# 04-SX1257.net
KiCad netlist of a schematic drawn in Altium Designer
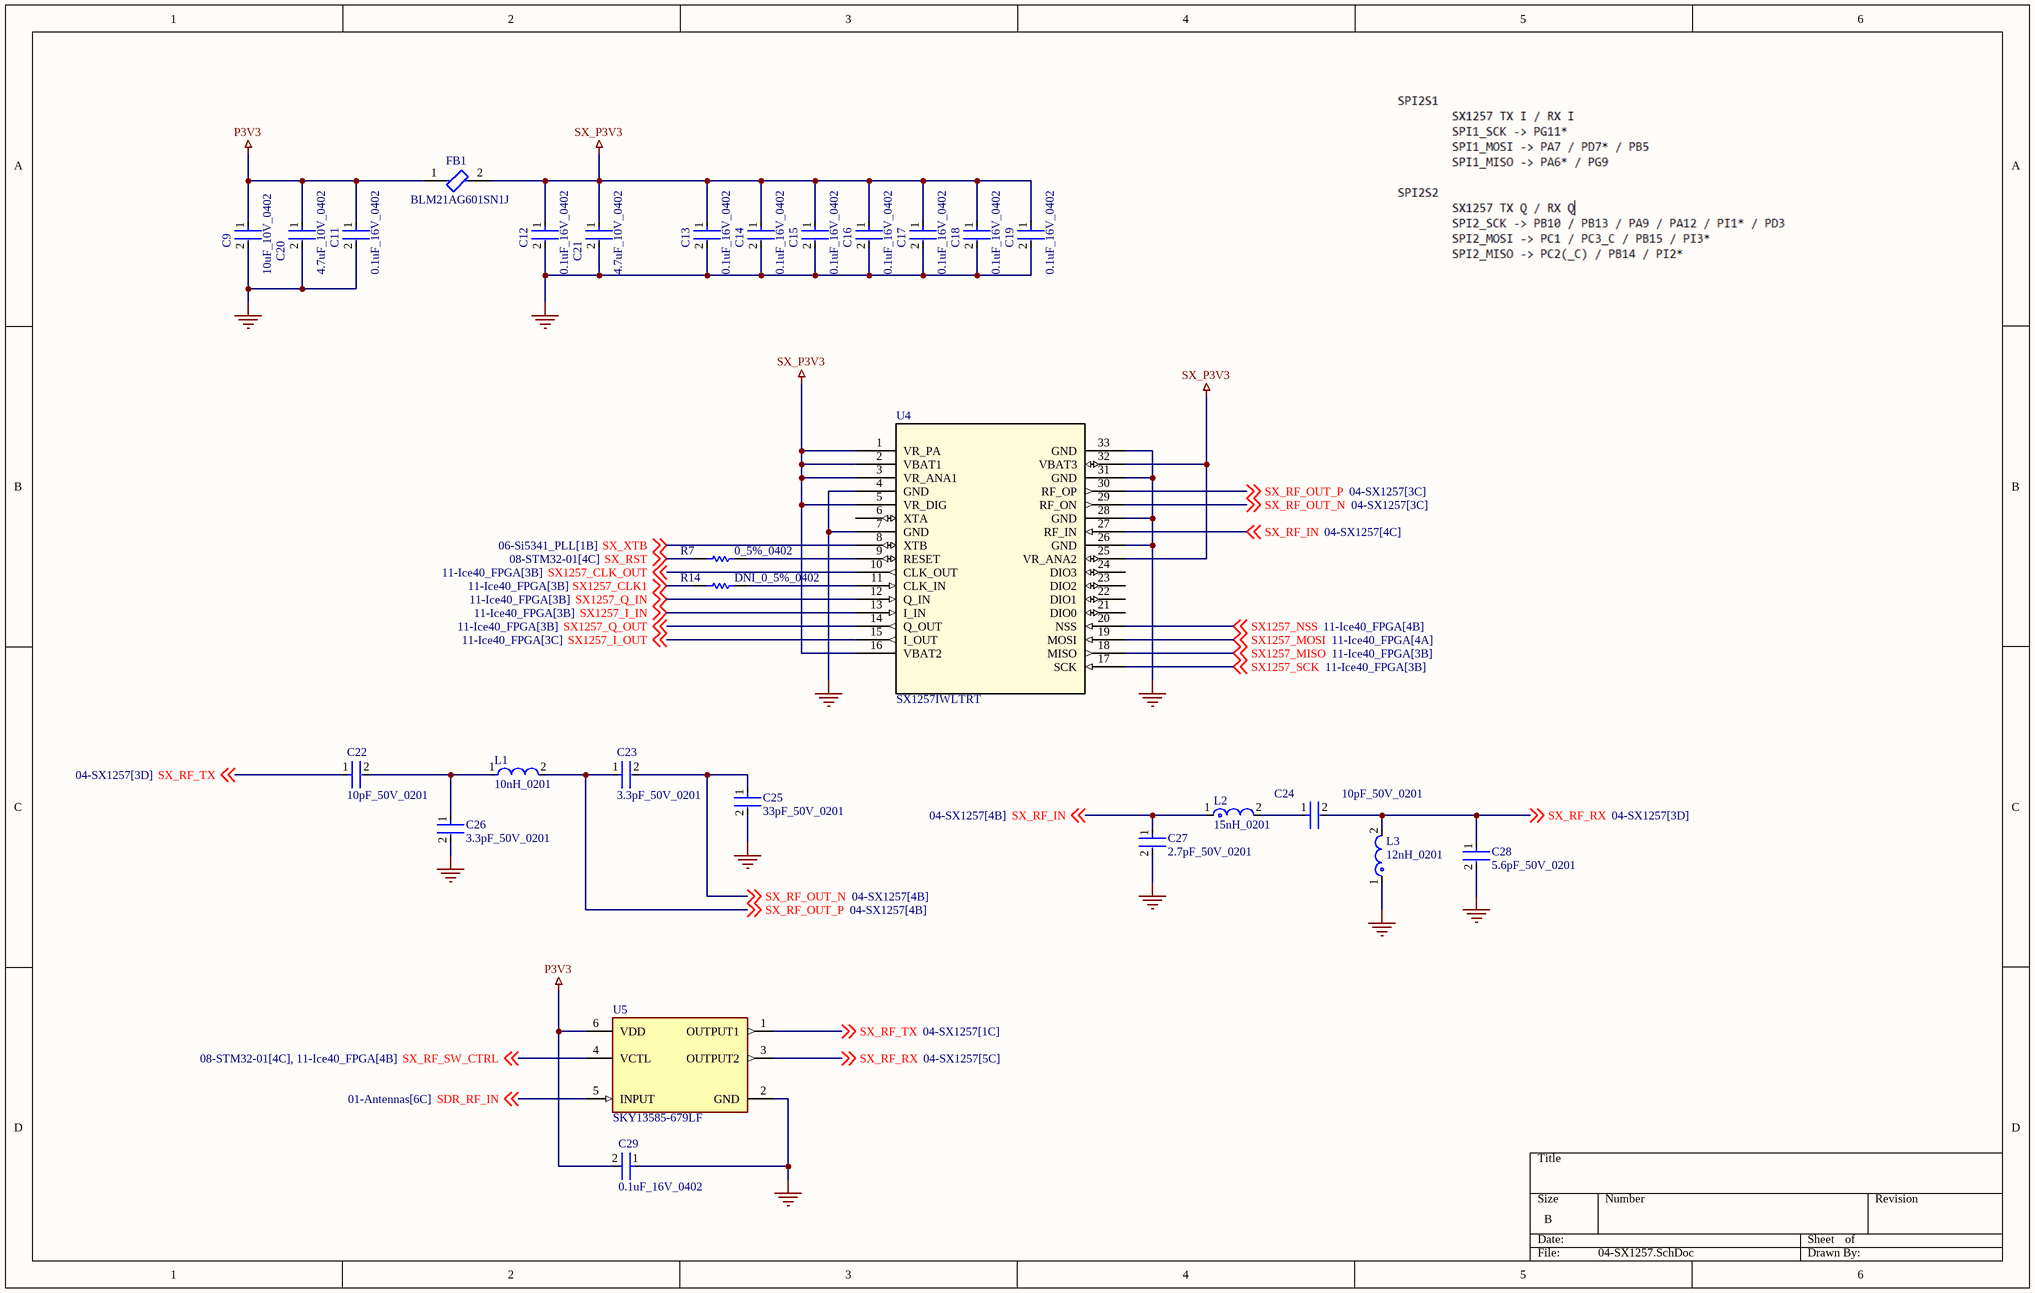
[diagram p0: 04-SX1257.SchDoc]

(export (version "E")
  (design (tool "Eeschema 10.0.6"))
  (components
    (comp (ref "C9")
      (value "10uF_10V_0402")
      (footprint "FP-CL05A106MP5NUNC-MFG")
      (description "CAP CER 10UF 10V X5R 0402")
      (fields
        (field (name "OCTOPART") "https://octopart.com/cl05a106mp5nunc-samsung-22457395")
        (field (name "TOLERANCE") "20%")
      )
      (libsource (lib "Altium Content Vault") (part "b4654b650e69147ec39a6b967a45e02"))
    )
    (comp (ref "C11")
      (value "0.1uF_16V_0402")
      (footprint "FP-C0402-BB-MFG")
      (description "CAP CER 0.1UF 16V 5% X7R 0402")
      (fields
        (field (name "MANUFACTURER") "Kemet")
        (field (name "MANUFACTURER PART NUMBER") "C0402C104J4RACTU")
      )
      (libsource (lib "Altium Content Vault") (part "b4654b650e69147ec39a6b967a45e02"))
    )
    (comp (ref "C12")
      (value "0.1uF_16V_0402")
      (footprint "FP-C0402-BB-MFG")
      (description "CAP CER 0.1UF 16V 5% X7R 0402")
      (fields
        (field (name "MANUFACTURER") "Kemet")
        (field (name "MANUFACTURER PART NUMBER") "C0402C104J4RACTU")
      )
      (libsource (lib "Altium Content Vault") (part "b4654b650e69147ec39a6b967a45e02"))
    )
    (comp (ref "C13")
      (value "0.1uF_16V_0402")
      (footprint "FP-C0402-BB-MFG")
      (description "CAP CER 0.1UF 16V 5% X7R 0402")
      (fields
        (field (name "MANUFACTURER") "Kemet")
        (field (name "MANUFACTURER PART NUMBER") "C0402C104J4RACTU")
      )
      (libsource (lib "Altium Content Vault") (part "b4654b650e69147ec39a6b967a45e02"))
    )
    (comp (ref "C14")
      (value "0.1uF_16V_0402")
      (footprint "FP-C0402-BB-MFG")
      (description "CAP CER 0.1UF 16V 5% X7R 0402")
      (fields
        (field (name "MANUFACTURER") "Kemet")
        (field (name "MANUFACTURER PART NUMBER") "C0402C104J4RACTU")
      )
      (libsource (lib "Altium Content Vault") (part "b4654b650e69147ec39a6b967a45e02"))
    )
    (comp (ref "C15")
      (value "0.1uF_16V_0402")
      (footprint "FP-C0402-BB-MFG")
      (description "CAP CER 0.1UF 16V 5% X7R 0402")
      (fields
        (field (name "MANUFACTURER") "Kemet")
        (field (name "MANUFACTURER PART NUMBER") "C0402C104J4RACTU")
      )
      (libsource (lib "Altium Content Vault") (part "b4654b650e69147ec39a6b967a45e02"))
    )
    (comp (ref "C16")
      (value "0.1uF_16V_0402")
      (footprint "FP-C0402-BB-MFG")
      (description "CAP CER 0.1UF 16V 5% X7R 0402")
      (fields
        (field (name "MANUFACTURER") "Kemet")
        (field (name "MANUFACTURER PART NUMBER") "C0402C104J4RACTU")
      )
      (libsource (lib "Altium Content Vault") (part "b4654b650e69147ec39a6b967a45e02"))
    )
    (comp (ref "C17")
      (value "0.1uF_16V_0402")
      (footprint "FP-C0402-BB-MFG")
      (description "CAP CER 0.1UF 16V 5% X7R 0402")
      (fields
        (field (name "MANUFACTURER") "Kemet")
        (field (name "MANUFACTURER PART NUMBER") "C0402C104J4RACTU")
      )
      (libsource (lib "Altium Content Vault") (part "b4654b650e69147ec39a6b967a45e02"))
    )
    (comp (ref "C18")
      (value "0.1uF_16V_0402")
      (footprint "FP-C0402-BB-MFG")
      (description "CAP CER 0.1UF 16V 5% X7R 0402")
      (fields
        (field (name "MANUFACTURER") "Kemet")
        (field (name "MANUFACTURER PART NUMBER") "C0402C104J4RACTU")
      )
      (libsource (lib "Altium Content Vault") (part "b4654b650e69147ec39a6b967a45e02"))
    )
    (comp (ref "C19")
      (value "0.1uF_16V_0402")
      (footprint "FP-C0402-BB-MFG")
      (description "CAP CER 0.1UF 16V 5% X7R 0402")
      (fields
        (field (name "MANUFACTURER") "Kemet")
        (field (name "MANUFACTURER PART NUMBER") "C0402C104J4RACTU")
      )
      (libsource (lib "Altium Content Vault") (part "b4654b650e69147ec39a6b967a45e02"))
    )
    (comp (ref "C20")
      (value "4.7uF_10V_0402")
      (footprint "FP-C1005-050-0_15-MFG")
      (description "CAP CER 4.7UF 10V X5R 0402")
      (fields (field (name "TOLERANCE") "10%"))
      (libsource (lib "Altium Content Vault") (part "b4654b650e69147ec39a6b967a45e02"))
    )
    (comp (ref "C21")
      (value "4.7uF_10V_0402")
      (footprint "FP-C1005-050-0_15-MFG")
      (description "CAP CER 4.7UF 10V X5R 0402")
      (fields (field (name "TOLERANCE") "10%"))
      (libsource (lib "Altium Content Vault") (part "b4654b650e69147ec39a6b967a45e02"))
    )
    (comp (ref "C22")
      (value "10pF_50V_0201")
      (footprint "FP-CGA1A-0_1-0_03-MFG")
      (description "Cap Ceramic 10pF 50V C0G 0.5pF Pad SMD 0201 125°C Automotive T/R")
      (libsource (lib "Altium Content Vault") (part "b4654b650e69147ec39a6b967a45e02"))
    )
    (comp (ref "C23")
      (value "3.3pF_50V_0201")
      (footprint "FP-GRM033-0_03-IPC_C")
      (description "Chip Multilayer Ceramic Capacitors for General Purpose, 0201, 3.3pF, C0G, 30ppm/°C, 0.25pF, 50V")
      (libsource (lib "Altium Content Vault") (part "b4654b650e69147ec39a6b967a45e02"))
    )
    (comp (ref "C24")
      (value "10pF_50V_0201")
      (footprint "FP-CGA1A-0_1-0_03-MFG")
      (description "Cap Ceramic 10pF 50V C0G 0.5pF Pad SMD 0201 125°C Automotive T/R")
      (libsource (lib "Altium Content Vault") (part "b4654b650e69147ec39a6b967a45e02"))
    )
    (comp (ref "C25")
      (value "33pF_50V_0201")
      (footprint "FP-CGA1A-0_1-0_03-MFG")
      (description "Cap Ceramic 33pF 50V C0G 5% Pad SMD 0201 125°C Automotive T/R")
      (fields (field (name "TOLERANCE") "5%"))
      (libsource (lib "Altium Content Vault") (part "b4654b650e69147ec39a6b967a45e02"))
    )
    (comp (ref "C26")
      (value "3.3pF_50V_0201")
      (footprint "FP-GRM033-0_03-IPC_C")
      (description "Chip Multilayer Ceramic Capacitors for General Purpose, 0201, 3.3pF, C0G, 30ppm/°C, 0.25pF, 50V")
      (libsource (lib "Altium Content Vault") (part "b4654b650e69147ec39a6b967a45e02"))
    )
    (comp (ref "C27")
      (value "2.7pF_50V_0201")
      (footprint "FP-GRM033-0_03-IPC_C")
      (description "Chip Multilayer Ceramic Capacitors for General Purpose, 0201, 2.7pF, C0G, 30ppm/°C, 0.25pF, 50V")
      (libsource (lib "Altium Content Vault") (part "b4654b650e69147ec39a6b967a45e02"))
    )
    (comp (ref "C28")
      (value "5.6pF_50V_0201")
      (footprint "FP-GRM033-0_03-MFG")
      (description "Chip Multilayer Ceramic Capacitors for General Purpose, 0201, 5.6pF, C0G, 30ppm/°C, 0.1pF, 50V")
      (libsource (lib "Altium Content Vault") (part "b4654b650e69147ec39a6b967a45e02"))
    )
    (comp (ref "C29")
      (value "0.1uF_16V_0402")
      (footprint "FP-C0402-BB-MFG")
      (description "CAP CER 0.1UF 16V 5% X7R 0402")
      (fields
        (field (name "MANUFACTURER") "Kemet")
        (field (name "MANUFACTURER PART NUMBER") "C0402C104J4RACTU")
      )
      (libsource (lib "Altium Content Vault") (part "b4654b650e69147ec39a6b967a45e02"))
    )
    (comp (ref "FB1")
      (value "BLM21AG601SN1J")
      (footprint "FP-BLM21-0_2-t0_85-e0_5-IPC_A")
      (description "Chip Ferrite Bead, 0805, 600Ω @ 100MHz, 0.2Ω, 25%, 700mA")
      (fields (field (name "TOLERANCE") "25%"))
      (libsource (lib "Altium Content Vault") (part "5f30dd21d616792df468990f7003faa"))
    )
    (comp (ref "L1")
      (value "10nH_0201")
      (footprint "FP-LQP03HQ_02-MFG")
      (description "Film type RF Inductor 10nH ±3% 300mA 0.4Ω 0201 (0603)")
      (fields (field (name "TOLERANCE") "3%"))
      (libsource (lib "Altium Content Vault") (part "725321dda6339637d4d059423bc1c3c"))
    )
    (comp (ref "L2")
      (value "15nH_0201")
      (footprint "FP-LQP03TG_02-IPC_C")
      (description "Film type RF Inductor 15nH ±5% 250mA 0.7Ω 0201 (0603)")
      (fields (field (name "TOLERANCE") "5%"))
      (libsource (lib "Altium Content Vault") (part "4cc4b267dca4c8e51f7102f422741d8"))
    )
    (comp (ref "L3")
      (value "12nH_0201")
      (footprint "FP-LQP03TG_02-MFG")
      (description "Film type RF Inductor 12nH ±5% 250mA 0.7Ω 0201 (0603)")
      (fields (field (name "TOLERANCE") "5%"))
      (libsource (lib "Altium Content Vault") (part "4cc4b267dca4c8e51f7102f422741d8"))
    )
    (comp (ref "R7")
      (value "0_5%_0402")
      (footprint "RESC1005X40X25NL05T10")
      (fields (field (name "MANUFACTURER") "Panasonic") (field (name "PART NUMBER") "ERJ-U020R00X"))
      (libsource (lib "Altium Content Vault") (part "RES"))
    )
    (comp (ref "R14")
      (value "DNI_0_5%_0402")
      (footprint "RESC1005X40X25NL05T10")
      (fields (field (name "MANUFACTURER") "Panasonic") (field (name "PART NUMBER") "ERJ-U020R00X"))
      (libsource (lib "Altium Content Vault") (part "RES"))
    )
    (comp (ref "U4")
      (value "SX1257IWLTRT")
      (footprint "MLPQW-32_SEM")
      (description "No Description Available")
      (fields (field (name "COPYRIGHT") "Copyright (C) 2023 Ultra Librarian. All rights reserved."))
      (libsource (lib "SX1257IWLTRT") (part "SX1257IWLTRT"))
    )
    (comp (ref "U5")
      (value "SKY13585-679LF")
      (footprint "FP-SKY13585-679LF-MFG")
      (description "IC RF SWITCH SPDT 6GHZ 6MLPD")
      (libsource (lib "Altium Content Vault") (part "e67e48af39ab44f3294fce00d3e4f12"))
    )
  )
  (nets
    (net (code "1") (name "GND") (class "Default")
      (node (ref "C11") (pin "2") (pinfunction "2_2") (pintype "passive"))
      (node (ref "C12") (pin "2") (pinfunction "2_2") (pintype "passive"))
      (node (ref "C13") (pin "2") (pinfunction "2_2") (pintype "passive"))
      (node (ref "C14") (pin "2") (pinfunction "2_2") (pintype "passive"))
      (node (ref "C15") (pin "2") (pinfunction "2_2") (pintype "passive"))
      (node (ref "C16") (pin "2") (pinfunction "2_2") (pintype "passive"))
      (node (ref "C17") (pin "2") (pinfunction "2_2") (pintype "passive"))
      (node (ref "C18") (pin "2") (pinfunction "2_2") (pintype "passive"))
      (node (ref "C19") (pin "2") (pinfunction "2_2") (pintype "passive"))
      (node (ref "C20") (pin "2") (pinfunction "2_2") (pintype "passive"))
      (node (ref "C21") (pin "2") (pinfunction "2_2") (pintype "passive"))
      (node (ref "C25") (pin "2") (pinfunction "2_2") (pintype "passive"))
      (node (ref "C26") (pin "2") (pinfunction "2_2") (pintype "passive"))
      (node (ref "C27") (pin "2") (pinfunction "2_2") (pintype "passive"))
      (node (ref "C28") (pin "2") (pinfunction "2_2") (pintype "passive"))
      (node (ref "C29") (pin "1") (pinfunction "1_1") (pintype "passive"))
      (node (ref "C9") (pin "2") (pinfunction "2_2") (pintype "passive"))
      (node (ref "L3") (pin "1") (pinfunction "1_1") (pintype "passive"))
      (node (ref "U4") (pin "26") (pinfunction "GND_26") (pintype "power_in"))
      (node (ref "U4") (pin "28") (pinfunction "GND_28") (pintype "power_in"))
      (node (ref "U4") (pin "31") (pinfunction "GND_31") (pintype "power_in"))
      (node (ref "U4") (pin "33") (pinfunction "GND_33") (pintype "power_in"))
      (node (ref "U4") (pin "4") (pinfunction "GND_4") (pintype "power_in"))
      (node (ref "U4") (pin "7") (pinfunction "GND_7") (pintype "power_in"))
      (node (ref "U5") (pin "2") (pinfunction "GND_2") (pintype "power_in"))
    )
    (net (code "2") (name "Net-(C22-Pad2)") (class "Default")
      (node (ref "C22") (pin "2") (pinfunction "2_2") (pintype "passive"))
      (node (ref "C26") (pin "1") (pinfunction "1_1") (pintype "passive"))
      (node (ref "L1") (pin "1") (pinfunction "1_1") (pintype "passive"))
    )
    (net (code "3") (name "Net-(C24-Pad1)") (class "Default")
      (node (ref "C24") (pin "1") (pinfunction "1_1") (pintype "passive"))
      (node (ref "L2") (pin "2") (pinfunction "2_2") (pintype "passive"))
    )
    (net (code "4") (name "Net-(U4-CLK_IN)") (class "Default")
      (node (ref "R14") (pin "2") (pinfunction "2_2") (pintype "passive"))
      (node (ref "U4") (pin "11") (pinfunction "CLK_IN_11") (pintype "input"))
    )
    (net (code "5") (name "Net-(U4-RESET)") (class "Default")
      (node (ref "R7") (pin "2") (pinfunction "2_2") (pintype "passive"))
      (node (ref "U4") (pin "9") (pinfunction "RESET_9") (pintype "bidirectional"))
    )
    (net (code "6") (name "P3V3") (class "Default")
      (node (ref "C11") (pin "1") (pinfunction "1_1") (pintype "passive"))
      (node (ref "C20") (pin "1") (pinfunction "1_1") (pintype "passive"))
      (node (ref "C29") (pin "2") (pinfunction "2_2") (pintype "passive"))
      (node (ref "C9") (pin "1") (pinfunction "1_1") (pintype "passive"))
      (node (ref "FB1") (pin "1") (pinfunction "1_1") (pintype "passive"))
      (node (ref "U5") (pin "6") (pinfunction "VDD_6") (pintype "power_in"))
    )
    (net (code "7") (name "SDR_RF_IN") (class "Default")
      (node (ref "U5") (pin "5") (pinfunction "INPUT_5") (pintype "input"))
    )
    (net (code "8") (name "SX1257_CLK1") (class "Default")
      (node (ref "R14") (pin "1") (pinfunction "1_1") (pintype "passive"))
    )
    (net (code "9") (name "SX1257_CLK_OUT") (class "Default")
      (node (ref "U4") (pin "10") (pinfunction "CLK_OUT_10") (pintype "output"))
    )
    (net (code "10") (name "SX1257_I_IN") (class "Default")
      (node (ref "U4") (pin "13") (pinfunction "I_IN_13") (pintype "input"))
    )
    (net (code "11") (name "SX1257_I_OUT") (class "Default")
      (node (ref "U4") (pin "15") (pinfunction "I_OUT_15") (pintype "output"))
    )
    (net (code "12") (name "SX1257_MISO") (class "Default")
      (node (ref "U4") (pin "18") (pinfunction "MISO_18") (pintype "output"))
    )
    (net (code "13") (name "SX1257_MOSI") (class "Default")
      (node (ref "U4") (pin "19") (pinfunction "MOSI_19") (pintype "input"))
    )
    (net (code "14") (name "SX1257_NSS") (class "Default")
      (node (ref "U4") (pin "20") (pinfunction "NSS_20") (pintype "input"))
    )
    (net (code "15") (name "SX1257_Q_IN") (class "Default")
      (node (ref "U4") (pin "12") (pinfunction "Q_IN_12") (pintype "input"))
    )
    (net (code "16") (name "SX1257_Q_OUT") (class "Default")
      (node (ref "U4") (pin "14") (pinfunction "Q_OUT_14") (pintype "output"))
    )
    (net (code "17") (name "SX1257_SCK") (class "Default")
      (node (ref "U4") (pin "17") (pinfunction "SCK_17") (pintype "input"))
    )
    (net (code "18") (name "SX_P3V3") (class "Default")
      (node (ref "C12") (pin "1") (pinfunction "1_1") (pintype "passive"))
      (node (ref "C13") (pin "1") (pinfunction "1_1") (pintype "passive"))
      (node (ref "C14") (pin "1") (pinfunction "1_1") (pintype "passive"))
      (node (ref "C15") (pin "1") (pinfunction "1_1") (pintype "passive"))
      (node (ref "C16") (pin "1") (pinfunction "1_1") (pintype "passive"))
      (node (ref "C17") (pin "1") (pinfunction "1_1") (pintype "passive"))
      (node (ref "C18") (pin "1") (pinfunction "1_1") (pintype "passive"))
      (node (ref "C19") (pin "1") (pinfunction "1_1") (pintype "passive"))
      (node (ref "C21") (pin "1") (pinfunction "1_1") (pintype "passive"))
      (node (ref "FB1") (pin "2") (pinfunction "2_2") (pintype "passive"))
      (node (ref "U4") (pin "1") (pinfunction "VR_PA_1") (pintype "power_in"))
      (node (ref "U4") (pin "16") (pinfunction "VBAT2_16") (pintype "power_in"))
      (node (ref "U4") (pin "2") (pinfunction "VBAT1_2") (pintype "power_in"))
      (node (ref "U4") (pin "25") (pinfunction "VR_ANA2_25") (pintype "bidirectional"))
      (node (ref "U4") (pin "3") (pinfunction "VR_ANA1_3") (pintype "power_in"))
      (node (ref "U4") (pin "32") (pinfunction "VBAT3_32") (pintype "bidirectional"))
      (node (ref "U4") (pin "5") (pinfunction "VR_DIG_5") (pintype "power_in"))
    )
    (net (code "19") (name "SX_RF_IN") (class "Default")
      (node (ref "C27") (pin "1") (pinfunction "1_1") (pintype "passive"))
      (node (ref "L2") (pin "1") (pinfunction "1_1") (pintype "passive"))
      (node (ref "U4") (pin "27") (pinfunction "RF_IN_27") (pintype "input"))
    )
    (net (code "20") (name "SX_RF_OUT_N") (class "Default")
      (node (ref "C23") (pin "2") (pinfunction "2_2") (pintype "passive"))
      (node (ref "C25") (pin "1") (pinfunction "1_1") (pintype "passive"))
      (node (ref "U4") (pin "29") (pinfunction "RF_ON_29") (pintype "output"))
    )
    (net (code "21") (name "SX_RF_OUT_P") (class "Default")
      (node (ref "C23") (pin "1") (pinfunction "1_1") (pintype "passive"))
      (node (ref "L1") (pin "2") (pinfunction "2_2") (pintype "passive"))
      (node (ref "U4") (pin "30") (pinfunction "RF_OP_30") (pintype "output"))
    )
    (net (code "22") (name "SX_RF_RX") (class "Default")
      (node (ref "C24") (pin "2") (pinfunction "2_2") (pintype "passive"))
      (node (ref "C28") (pin "1") (pinfunction "1_1") (pintype "passive"))
      (node (ref "L3") (pin "2") (pinfunction "2_2") (pintype "passive"))
      (node (ref "U5") (pin "3") (pinfunction "OUTPUT2_3") (pintype "output"))
    )
    (net (code "23") (name "SX_RF_SW_CTRL") (class "Default")
      (node (ref "U5") (pin "4") (pinfunction "VCTL_4") (pintype "power_in"))
    )
    (net (code "24") (name "SX_RF_TX") (class "Default")
      (node (ref "C22") (pin "1") (pinfunction "1_1") (pintype "passive"))
      (node (ref "U5") (pin "1") (pinfunction "OUTPUT1_1") (pintype "output"))
    )
    (net (code "25") (name "SX_RST") (class "Default")
      (node (ref "R7") (pin "1") (pinfunction "1_1") (pintype "passive"))
    )
    (net (code "26") (name "SX_XTB") (class "Default")
      (node (ref "U4") (pin "8") (pinfunction "XTB_8") (pintype "bidirectional"))
    )
    (net (code "27") (name "unconnected-(U4-DIO0-Pad21)") (class "Default")
      (node (ref "U4") (pin "21") (pinfunction "DIO0_21") (pintype "bidirectional"))
    )
    (net (code "28") (name "unconnected-(U4-DIO1-Pad22)") (class "Default")
      (node (ref "U4") (pin "22") (pinfunction "DIO1_22") (pintype "bidirectional"))
    )
    (net (code "29") (name "unconnected-(U4-DIO2-Pad23)") (class "Default")
      (node (ref "U4") (pin "23") (pinfunction "DIO2_23") (pintype "bidirectional"))
    )
    (net (code "30") (name "unconnected-(U4-DIO3-Pad24)") (class "Default")
      (node (ref "U4") (pin "24") (pinfunction "DIO3_24") (pintype "bidirectional"))
    )
    (net (code "31") (name "unconnected-(U4-XTA-Pad6)") (class "Default")
      (node (ref "U4") (pin "6") (pinfunction "XTA_6") (pintype "bidirectional"))
    )
  )
)
